# Sheet1.net
KiCad netlist of a schematic drawn in Altium Designer
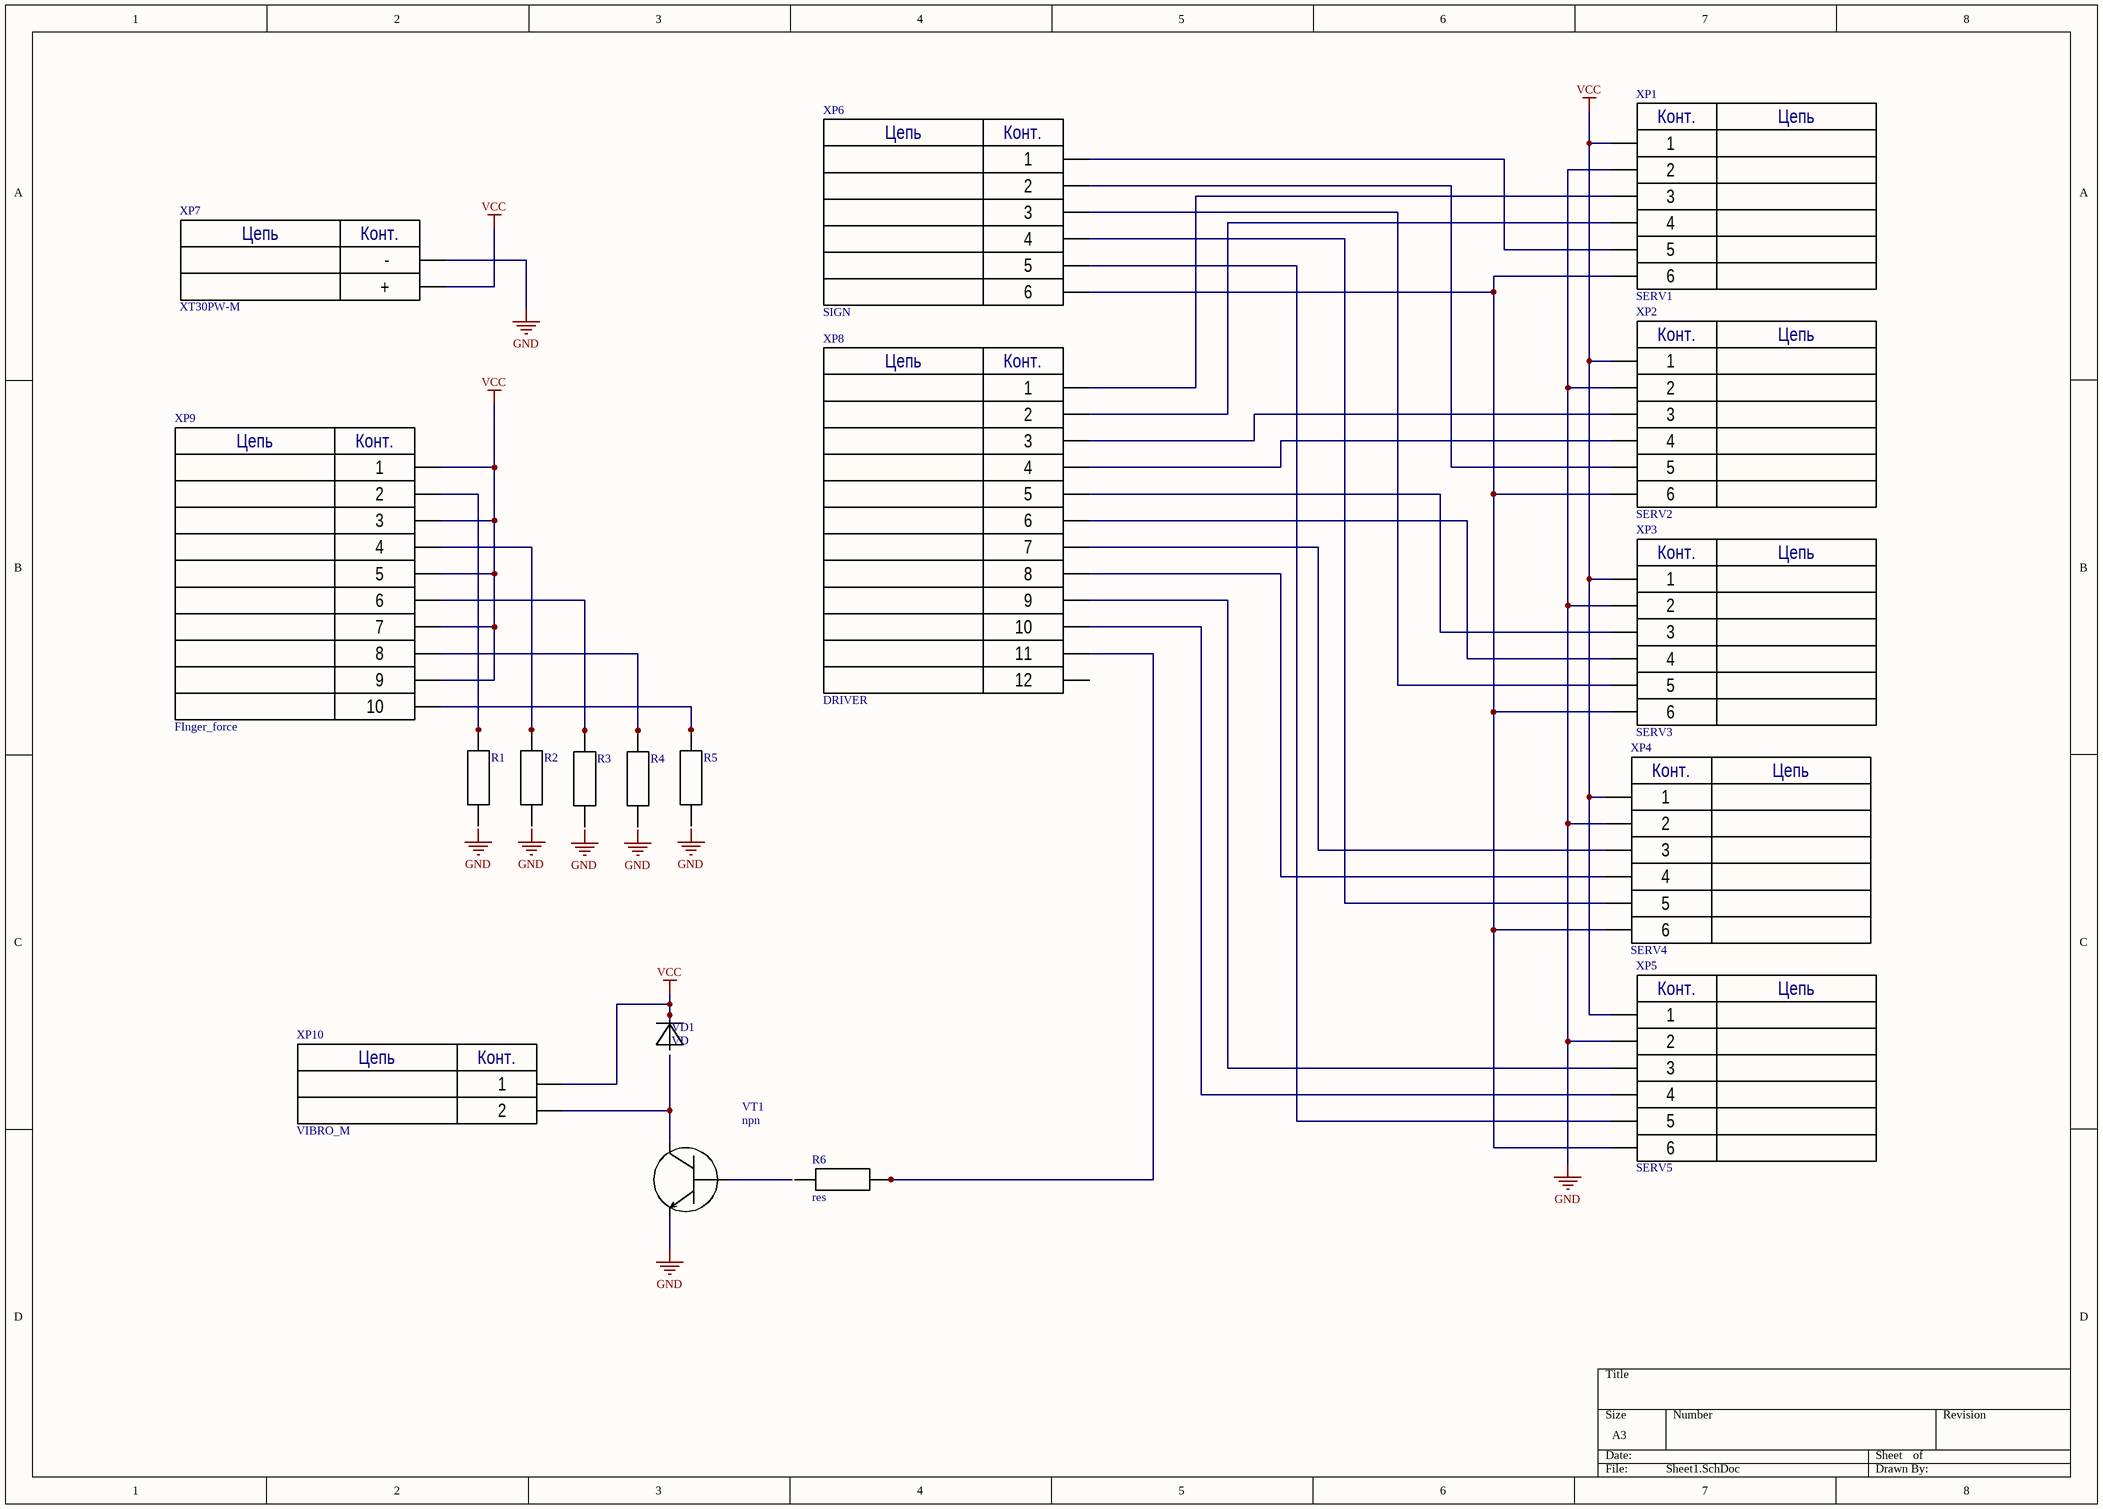
[diagram p0: Sheet1.SchDoc]

(export (version "E")
  (design (tool "Eeschema 10.0.6"))
  (components
    (comp (ref "R1") (value "res") (footprint "RES") (libsource (lib "Pakage_lib") (part "res")))
    (comp (ref "R2") (value "res") (footprint "RES") (libsource (lib "Pakage_lib") (part "res")))
    (comp (ref "R3") (value "res") (footprint "RES") (libsource (lib "Pakage_lib") (part "res")))
    (comp (ref "R4") (value "res") (footprint "RES") (libsource (lib "Pakage_lib") (part "res")))
    (comp (ref "R5") (value "res") (footprint "RES") (libsource (lib "Pakage_lib") (part "res")))
    (comp (ref "R6") (value "res") (footprint "RES") (libsource (lib "Pakage_lib") (part "res")))
    (comp (ref "VD1") (value "VD") (footprint "DIODE") (libsource (lib "Pakage_lib") (part "VD")))
    (comp (ref "VT1") (value "npn") (footprint "TO-92") (libsource (lib "Pakage_lib") (part "npn")))
    (comp (ref "XP1")
      (value "SERV1")
      (footprint "PLS-6")
      (description "PLS-6")
      (libsource (lib "Разъемы") (part "PLS-6"))
    )
    (comp (ref "XP2")
      (value "SERV2")
      (footprint "PLS-6")
      (description "PLS-6")
      (libsource (lib "Разъемы") (part "PLS-6"))
    )
    (comp (ref "XP3")
      (value "SERV3")
      (footprint "PLS-6")
      (description "PLS-6")
      (libsource (lib "Разъемы") (part "PLS-6"))
    )
    (comp (ref "XP4")
      (value "SERV4")
      (footprint "PLS-6")
      (description "PLS-6")
      (libsource (lib "Разъемы") (part "PLS-6"))
    )
    (comp (ref "XP5")
      (value "SERV5")
      (footprint "PLS-6")
      (description "PLS-6")
      (libsource (lib "Разъемы") (part "PLS-6"))
    )
    (comp (ref "XP6")
      (value "SIGN")
      (footprint "PLS-6")
      (description "PLS-6")
      (libsource (lib "Разъемы") (part "PLS-6"))
    )
    (comp (ref "XP7")
      (value "XT30PW-M")
      (footprint "XT30U-F")
      (libsource (lib "Integrated_Library1") (part "XT30PW-M"))
    )
    (comp (ref "XP8")
      (value "DRIVER")
      (footprint "PLD-12")
      (description "PLD-12")
      (libsource (lib "Integrated_Library1") (part "PLD-12"))
    )
    (comp (ref "XP9")
      (value "FInger_force")
      (footprint "PLD-10")
      (description "PLD-10")
      (libsource (lib "Integrated_Library1") (part "PLD-10"))
    )
    (comp (ref "XP10")
      (value "VIBRO_M")
      (footprint "PLS-2")
      (description "PLS-2")
      (libsource (lib "Разъемы") (part "PLS-2"))
    )
  )
  (nets
    (net (code "1") (name "GND") (class "Default")
      (node (ref "VT1") (pin "3") (pinfunction "12_3") (pintype "passive"))
      (node (ref "XP1") (pin "2") (pinfunction "2_2") (pintype "passive"))
      (node (ref "XP2") (pin "2") (pinfunction "2_2") (pintype "passive"))
      (node (ref "XP3") (pin "2") (pinfunction "2_2") (pintype "passive"))
      (node (ref "XP4") (pin "2") (pinfunction "2_2") (pintype "passive"))
      (node (ref "XP5") (pin "2") (pinfunction "2_2") (pintype "passive"))
      (node (ref "XP7") (pin "1") (pinfunction "-_1") (pintype "passive"))
    )
    (net (code "2") (name "Net-(R1-Pad2)") (class "Default")
      (node (ref "R1") (pin "2") (pinfunction "2_2") (pintype "passive"))
      (node (ref "XP9") (pin "2") (pinfunction "2_2") (pintype "passive"))
    )
    (net (code "3") (name "Net-(R2-Pad2)") (class "Default")
      (node (ref "R2") (pin "2") (pinfunction "2_2") (pintype "passive"))
      (node (ref "XP9") (pin "4") (pinfunction "4_4") (pintype "passive"))
    )
    (net (code "4") (name "Net-(R3-Pad2)") (class "Default")
      (node (ref "R3") (pin "2") (pinfunction "2_2") (pintype "passive"))
      (node (ref "XP9") (pin "6") (pinfunction "6_6") (pintype "passive"))
    )
    (net (code "5") (name "Net-(R4-Pad2)") (class "Default")
      (node (ref "R4") (pin "2") (pinfunction "2_2") (pintype "passive"))
      (node (ref "XP9") (pin "8") (pinfunction "8_8") (pintype "passive"))
    )
    (net (code "6") (name "Net-(R5-Pad2)") (class "Default")
      (node (ref "R5") (pin "2") (pinfunction "2_2") (pintype "passive"))
      (node (ref "XP9") (pin "10") (pinfunction "10_10") (pintype "passive"))
    )
    (net (code "7") (name "Net-(R6-Pad2)") (class "Default")
      (node (ref "R6") (pin "2") (pinfunction "2_2") (pintype "passive"))
      (node (ref "XP8") (pin "11") (pinfunction "11_11") (pintype "passive"))
    )
    (net (code "8") (name "Net-(VT1-11)") (class "Default")
      (node (ref "VT1") (pin "1") (pinfunction "11_1") (pintype "passive"))
      (node (ref "XP10") (pin "2") (pinfunction "2_2") (pintype "passive"))
    )
    (net (code "9") (name "Net-(XP1-Pad3)") (class "Default")
      (node (ref "XP1") (pin "3") (pinfunction "3_3") (pintype "passive"))
      (node (ref "XP8") (pin "1") (pinfunction "1_1") (pintype "passive"))
    )
    (net (code "10") (name "Net-(XP1-Pad4)") (class "Default")
      (node (ref "XP1") (pin "4") (pinfunction "4_4") (pintype "passive"))
      (node (ref "XP8") (pin "2") (pinfunction "2_2") (pintype "passive"))
    )
    (net (code "11") (name "Net-(XP1-Pad5)") (class "Default")
      (node (ref "XP1") (pin "5") (pinfunction "5_5") (pintype "passive"))
      (node (ref "XP6") (pin "1") (pinfunction "1_1") (pintype "passive"))
    )
    (net (code "12") (name "Net-(XP1-Pad6)") (class "Default")
      (node (ref "XP1") (pin "6") (pinfunction "6_6") (pintype "passive"))
      (node (ref "XP2") (pin "6") (pinfunction "6_6") (pintype "passive"))
      (node (ref "XP3") (pin "6") (pinfunction "6_6") (pintype "passive"))
      (node (ref "XP4") (pin "6") (pinfunction "6_6") (pintype "passive"))
      (node (ref "XP5") (pin "6") (pinfunction "6_6") (pintype "passive"))
      (node (ref "XP6") (pin "6") (pinfunction "6_6") (pintype "passive"))
    )
    (net (code "13") (name "Net-(XP2-Pad3)") (class "Default")
      (node (ref "XP2") (pin "3") (pinfunction "3_3") (pintype "passive"))
      (node (ref "XP8") (pin "3") (pinfunction "3_3") (pintype "passive"))
    )
    (net (code "14") (name "Net-(XP2-Pad4)") (class "Default")
      (node (ref "XP2") (pin "4") (pinfunction "4_4") (pintype "passive"))
      (node (ref "XP8") (pin "4") (pinfunction "4_4") (pintype "passive"))
    )
    (net (code "15") (name "Net-(XP2-Pad5)") (class "Default")
      (node (ref "XP2") (pin "5") (pinfunction "5_5") (pintype "passive"))
      (node (ref "XP6") (pin "2") (pinfunction "2_2") (pintype "passive"))
    )
    (net (code "16") (name "Net-(XP3-Pad3)") (class "Default")
      (node (ref "XP3") (pin "3") (pinfunction "3_3") (pintype "passive"))
      (node (ref "XP8") (pin "5") (pinfunction "5_5") (pintype "passive"))
    )
    (net (code "17") (name "Net-(XP3-Pad4)") (class "Default")
      (node (ref "XP3") (pin "4") (pinfunction "4_4") (pintype "passive"))
      (node (ref "XP8") (pin "6") (pinfunction "6_6") (pintype "passive"))
    )
    (net (code "18") (name "Net-(XP3-Pad5)") (class "Default")
      (node (ref "XP3") (pin "5") (pinfunction "5_5") (pintype "passive"))
      (node (ref "XP6") (pin "3") (pinfunction "3_3") (pintype "passive"))
    )
    (net (code "19") (name "Net-(XP4-Pad3)") (class "Default")
      (node (ref "XP4") (pin "3") (pinfunction "3_3") (pintype "passive"))
      (node (ref "XP8") (pin "7") (pinfunction "7_7") (pintype "passive"))
    )
    (net (code "20") (name "Net-(XP4-Pad4)") (class "Default")
      (node (ref "XP4") (pin "4") (pinfunction "4_4") (pintype "passive"))
      (node (ref "XP8") (pin "8") (pinfunction "8_8") (pintype "passive"))
    )
    (net (code "21") (name "Net-(XP4-Pad5)") (class "Default")
      (node (ref "XP4") (pin "5") (pinfunction "5_5") (pintype "passive"))
      (node (ref "XP6") (pin "4") (pinfunction "4_4") (pintype "passive"))
    )
    (net (code "22") (name "Net-(XP5-Pad3)") (class "Default")
      (node (ref "XP5") (pin "3") (pinfunction "3_3") (pintype "passive"))
      (node (ref "XP8") (pin "9") (pinfunction "9_9") (pintype "passive"))
    )
    (net (code "23") (name "Net-(XP5-Pad4)") (class "Default")
      (node (ref "XP5") (pin "4") (pinfunction "4_4") (pintype "passive"))
      (node (ref "XP8") (pin "10") (pinfunction "10_10") (pintype "passive"))
    )
    (net (code "24") (name "Net-(XP5-Pad5)") (class "Default")
      (node (ref "XP5") (pin "5") (pinfunction "5_5") (pintype "passive"))
      (node (ref "XP6") (pin "5") (pinfunction "5_5") (pintype "passive"))
    )
    (net (code "25") (name "VCC") (class "Default")
      (node (ref "VD1") (pin "2") (pinfunction "4_2") (pintype "passive"))
      (node (ref "XP1") (pin "1") (pinfunction "1_1") (pintype "passive"))
      (node (ref "XP10") (pin "1") (pinfunction "1_1") (pintype "passive"))
      (node (ref "XP2") (pin "1") (pinfunction "1_1") (pintype "passive"))
      (node (ref "XP3") (pin "1") (pinfunction "1_1") (pintype "passive"))
      (node (ref "XP4") (pin "1") (pinfunction "1_1") (pintype "passive"))
      (node (ref "XP5") (pin "1") (pinfunction "1_1") (pintype "passive"))
      (node (ref "XP7") (pin "2") (pinfunction "+_2") (pintype "passive"))
      (node (ref "XP9") (pin "1") (pinfunction "1_1") (pintype "passive"))
      (node (ref "XP9") (pin "3") (pinfunction "3_3") (pintype "passive"))
      (node (ref "XP9") (pin "5") (pinfunction "5_5") (pintype "passive"))
      (node (ref "XP9") (pin "7") (pinfunction "7_7") (pintype "passive"))
      (node (ref "XP9") (pin "9") (pinfunction "9_9") (pintype "passive"))
    )
    (net (code "26") (name "unconnected-(R1-5-Pad1)") (class "Default")
      (node (ref "R1") (pin "1") (pinfunction "5_1") (pintype "passive"))
    )
    (net (code "27") (name "unconnected-(R2-5-Pad1)") (class "Default")
      (node (ref "R2") (pin "1") (pinfunction "5_1") (pintype "passive"))
    )
    (net (code "28") (name "unconnected-(R3-5-Pad1)") (class "Default")
      (node (ref "R3") (pin "1") (pinfunction "5_1") (pintype "passive"))
    )
    (net (code "29") (name "unconnected-(R4-5-Pad1)") (class "Default")
      (node (ref "R4") (pin "1") (pinfunction "5_1") (pintype "passive"))
    )
    (net (code "30") (name "unconnected-(R5-5-Pad1)") (class "Default")
      (node (ref "R5") (pin "1") (pinfunction "5_1") (pintype "passive"))
    )
    (net (code "31") (name "unconnected-(R6-5-Pad1)") (class "Default")
      (node (ref "R6") (pin "1") (pinfunction "5_1") (pintype "passive"))
    )
    (net (code "32") (name "unconnected-(VD1-Pad1)") (class "Default")
      (node (ref "VD1") (pin "1") (pinfunction "1_1") (pintype "passive"))
    )
    (net (code "33") (name "unconnected-(VT1-13-Pad2)") (class "Default")
      (node (ref "VT1") (pin "2") (pinfunction "13_2") (pintype "passive"))
    )
    (net (code "34") (name "unconnected-(XP8-Pad12)") (class "Default")
      (node (ref "XP8") (pin "12") (pinfunction "12_12") (pintype "passive"))
    )
  )
)
